# arm_femur_wLED_smd.net
KiCad netlist of a schematic drawn in EAGLE
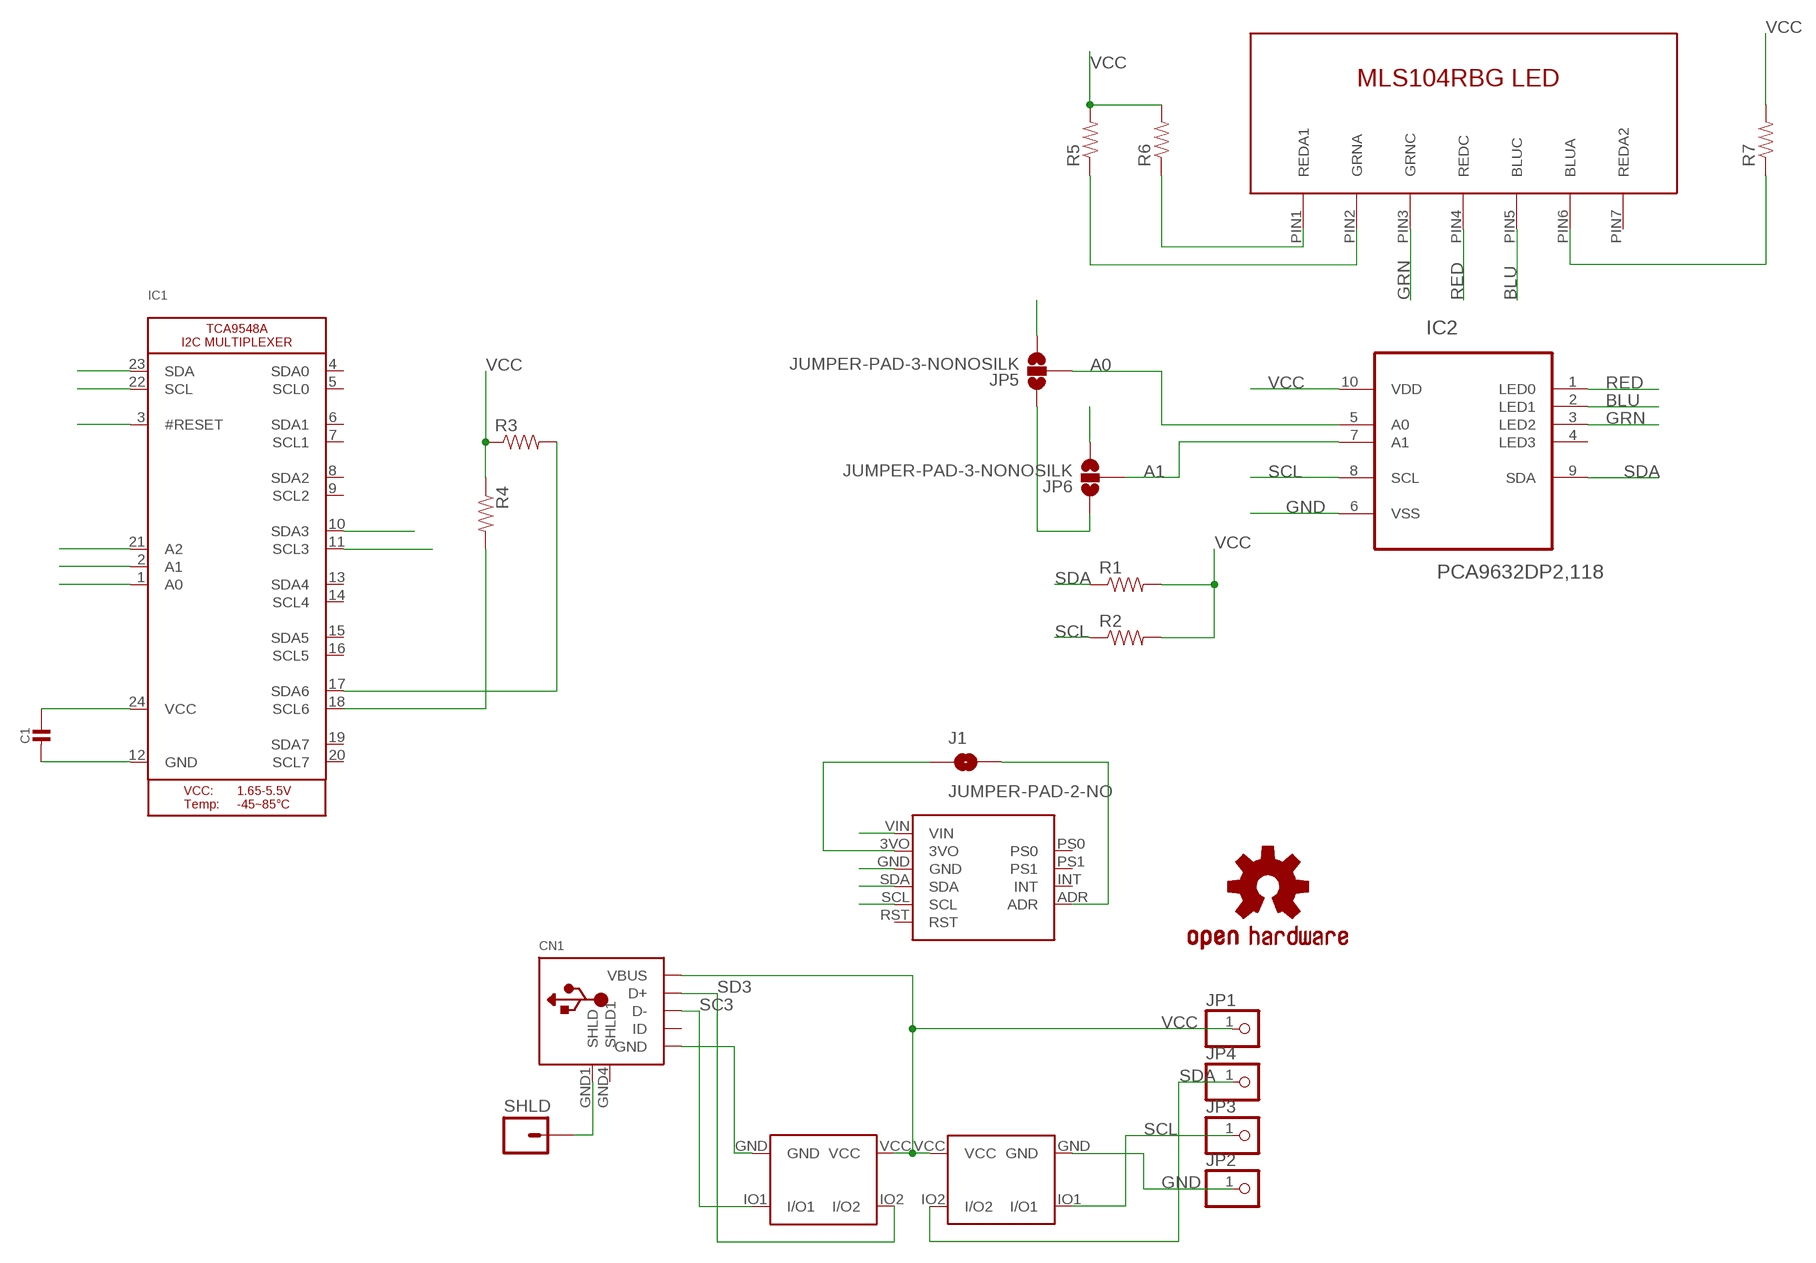
[diagram p0: schematic, sheet 1]

(export (version "E")
  (design (tool "Eeschema 10.0.6"))
  (components
    (comp (ref "C1")
      (value "CAP_CERAMIC0805-NOTHERMALS")
      (footprint "eagle-import:0805_NOTHERMALS")
      (libsource (lib "eagle-import") (part "CAP_CERAMIC0805-NOTHERMALS"))
    )
    (comp (ref "CN1")
      (value "USB")
      (footprint "eagle-import:USB-MINIB-THM-MOLEX_NOSLK")
      (libsource (lib "eagle-import") (part "USB"))
    )
    (comp (ref "IC1")
      (value "TCA9548A")
      (footprint "eagle-import:TSSOP24")
      (libsource (lib "eagle-import") (part "TCA9548A"))
    )
    (comp (ref "IC2")
      (value "PCA9632DP2,118")
      (footprint "eagle-import:SOP50P490X110-10N")
      (libsource (lib "eagle-import") (part "PCA9632DP2,118"))
    )
    (comp (ref "J1")
      (value "JUMPER-PAD-2-NO")
      (footprint "eagle-import:PAD-JUMPER-2-NO_NO_SILK")
      (libsource (lib "eagle-import") (part "JUMPER-PAD-2-NO"))
    )
    (comp (ref "JP1")
      (value "PINHD-1X1CB")
      (footprint "eagle-import:1X01-CLEANBIG")
      (libsource (lib "eagle-import") (part "PINHD-1X1CB"))
    )
    (comp (ref "JP2")
      (value "PINHD-1X1CB")
      (footprint "eagle-import:1X01-CLEANBIG")
      (libsource (lib "eagle-import") (part "PINHD-1X1CB"))
    )
    (comp (ref "JP3")
      (value "PINHD-1X1CB")
      (footprint "eagle-import:1X01-CLEANBIG")
      (libsource (lib "eagle-import") (part "PINHD-1X1CB"))
    )
    (comp (ref "JP4")
      (value "PINHD-1X1CB")
      (footprint "eagle-import:1X01-CLEANBIG")
      (libsource (lib "eagle-import") (part "PINHD-1X1CB"))
    )
    (comp (ref "JP5")
      (value "JUMPER-PAD-3-NONOSILK")
      (footprint "eagle-import:PAD-JUMPER-3-NO_NO_SILK")
      (libsource (lib "eagle-import") (part "JUMPER-PAD-3-NONOSILK"))
    )
    (comp (ref "JP6")
      (value "JUMPER-PAD-3-NONOSILK")
      (footprint "eagle-import:PAD-JUMPER-3-NO_NO_SILK")
      (libsource (lib "eagle-import") (part "JUMPER-PAD-3-NONOSILK"))
    )
    (comp (ref "LOGO1")
      (value "OSHW-LOGOS")
      (footprint "eagle-import:OSHW-LOGO-S")
      (libsource (lib "eagle-import") (part "OSHW-LOGOS"))
    )
    (comp (ref "R1")
      (value "RESISTOR0603-RES")
      (footprint "eagle-import:0603-RES")
      (libsource (lib "eagle-import") (part "RESISTOR0603-RES"))
    )
    (comp (ref "R2")
      (value "RESISTOR0603-RES")
      (footprint "eagle-import:0603-RES")
      (libsource (lib "eagle-import") (part "RESISTOR0603-RES"))
    )
    (comp (ref "R3")
      (value "RESISTOR0603-RES")
      (footprint "eagle-import:0603-RES")
      (libsource (lib "eagle-import") (part "RESISTOR0603-RES"))
    )
    (comp (ref "R4")
      (value "RESISTOR0603-RES")
      (footprint "eagle-import:0603-RES")
      (libsource (lib "eagle-import") (part "RESISTOR0603-RES"))
    )
    (comp (ref "R5")
      (value "RESISTOR0603-RES")
      (footprint "eagle-import:0603-RES")
      (libsource (lib "eagle-import") (part "RESISTOR0603-RES"))
    )
    (comp (ref "R6")
      (value "RESISTOR0603-RES")
      (footprint "eagle-import:0603-RES")
      (libsource (lib "eagle-import") (part "RESISTOR0603-RES"))
    )
    (comp (ref "R7")
      (value "RESISTOR0603-RES")
      (footprint "eagle-import:0603-RES")
      (libsource (lib "eagle-import") (part "RESISTOR0603-RES"))
    )
    (comp (ref "SHLD")
      (value "M01PTH")
      (footprint "eagle-import:1X01")
      (libsource (lib "eagle-import") (part "M01PTH"))
    )
    (comp (ref "U$1")
      (value "BNO_055_BKOUT")
      (footprint "eagle-import:BNO_BKOUT")
      (libsource (lib "eagle-import") (part "BNO_055_BKOUT"))
    )
    (comp (ref "U$2")
      (value "MSL0104RGB")
      (footprint "eagle-import:7-SMD")
      (libsource (lib "eagle-import") (part "MSL0104RGB"))
    )
    (comp (ref "U$3")
      (value "TVS_ARRAY_CD143A")
      (footprint "eagle-import:SOT-143")
      (libsource (lib "eagle-import") (part "TVS_ARRAY_CD143A"))
    )
    (comp (ref "U$4")
      (value "TVS_ARRAY_CD143A")
      (footprint "eagle-import:SOT-143")
      (libsource (lib "eagle-import") (part "TVS_ARRAY_CD143A"))
    )
  )
  (nets
    (net (code "1") (name "/A0") (class "Default")
      (node (ref "IC2") (pin "5") (pinfunction "A0_5") (pintype "input"))
      (node (ref "JP5") (pin "2") (pinfunction "2_2") (pintype "passive"))
    )
    (net (code "2") (name "/A1") (class "Default")
      (node (ref "IC2") (pin "7") (pinfunction "A1_7") (pintype "input"))
      (node (ref "JP6") (pin "2") (pinfunction "2_2") (pintype "passive"))
    )
    (net (code "3") (name "/BLU") (class "Default")
      (node (ref "IC2") (pin "2") (pinfunction "LED1_2") (pintype "output"))
      (node (ref "U$2") (pin "PIN5") (pinfunction "BLUC_PIN5") (pintype "bidirectional"))
    )
    (net (code "4") (name "/GND") (class "Default")
      (node (ref "C1") (pin "2") (pinfunction "2_2") (pintype "passive"))
      (node (ref "CN1") (pin "GND") (pinfunction "GND_GND") (pintype "power_in"))
      (node (ref "IC1") (pin "12") (pinfunction "GND_12") (pintype "bidirectional"))
      (node (ref "IC1") (pin "2") (pinfunction "A1_2") (pintype "bidirectional"))
      (node (ref "IC1") (pin "21") (pinfunction "A2_21") (pintype "bidirectional"))
      (node (ref "IC2") (pin "6") (pinfunction "VSS_6") (pintype "power_in"))
      (node (ref "JP2") (pin "1") (pinfunction "1_1") (pintype "passive"))
      (node (ref "JP5") (pin "1") (pinfunction "1_1") (pintype "passive"))
      (node (ref "JP6") (pin "1") (pinfunction "1_1") (pintype "passive"))
      (node (ref "U$1") (pin "GND") (pinfunction "GND_GND") (pintype "bidirectional"))
      (node (ref "U$3") (pin "GND") (pinfunction "GND_GND") (pintype "power_in"))
      (node (ref "U$4") (pin "GND") (pinfunction "GND_GND") (pintype "power_in"))
    )
    (net (code "5") (name "/GRN") (class "Default")
      (node (ref "IC2") (pin "3") (pinfunction "LED2_3") (pintype "output"))
      (node (ref "U$2") (pin "PIN3") (pinfunction "GRNC_PIN3") (pintype "bidirectional"))
    )
    (net (code "6") (name "/RED") (class "Default")
      (node (ref "IC2") (pin "1") (pinfunction "LED0_1") (pintype "output"))
      (node (ref "U$2") (pin "PIN4") (pinfunction "REDC_PIN4") (pintype "bidirectional"))
    )
    (net (code "7") (name "/SC3") (class "Default")
      (node (ref "CN1") (pin "D-") (pinfunction "D-_D-") (pintype "bidirectional"))
      (node (ref "IC1") (pin "11") (pinfunction "SCL3_11") (pintype "bidirectional"))
      (node (ref "U$4") (pin "IO1") (pinfunction "I/O1_IO1") (pintype "bidirectional"))
    )
    (net (code "8") (name "/SC6") (class "Default")
      (node (ref "IC1") (pin "18") (pinfunction "SCL6_18") (pintype "bidirectional"))
      (node (ref "R4") (pin "2") (pinfunction "2_2") (pintype "passive"))
      (node (ref "U$1") (pin "SCL") (pinfunction "SCL_SCL") (pintype "bidirectional"))
    )
    (net (code "9") (name "/SCL") (class "Default")
      (node (ref "IC1") (pin "22") (pinfunction "SCL_22") (pintype "bidirectional"))
      (node (ref "IC2") (pin "8") (pinfunction "SCL_8") (pintype "input"))
      (node (ref "JP3") (pin "1") (pinfunction "1_1") (pintype "passive"))
      (node (ref "R2") (pin "1") (pinfunction "1_1") (pintype "passive"))
      (node (ref "U$3") (pin "IO1") (pinfunction "I/O1_IO1") (pintype "bidirectional"))
    )
    (net (code "10") (name "/SD3") (class "Default")
      (node (ref "CN1") (pin "D+") (pinfunction "D+_D+") (pintype "bidirectional"))
      (node (ref "IC1") (pin "10") (pinfunction "SDA3_10") (pintype "bidirectional"))
      (node (ref "U$4") (pin "IO2") (pinfunction "I/O2_IO2") (pintype "bidirectional"))
    )
    (net (code "11") (name "/SD6") (class "Default")
      (node (ref "IC1") (pin "17") (pinfunction "SDA6_17") (pintype "bidirectional"))
      (node (ref "R3") (pin "2") (pinfunction "2_2") (pintype "passive"))
      (node (ref "U$1") (pin "SDA") (pinfunction "SDA_SDA") (pintype "bidirectional"))
    )
    (net (code "12") (name "/SDA") (class "Default")
      (node (ref "IC1") (pin "23") (pinfunction "SDA_23") (pintype "bidirectional"))
      (node (ref "IC2") (pin "9") (pinfunction "SDA_9") (pintype "bidirectional"))
      (node (ref "JP4") (pin "1") (pinfunction "1_1") (pintype "passive"))
      (node (ref "R1") (pin "1") (pinfunction "1_1") (pintype "passive"))
      (node (ref "U$3") (pin "IO2") (pinfunction "I/O2_IO2") (pintype "bidirectional"))
    )
    (net (code "13") (name "/VCC") (class "Default")
      (node (ref "C1") (pin "1") (pinfunction "1_1") (pintype "passive"))
      (node (ref "CN1") (pin "VBUS") (pinfunction "VBUS_VBUS") (pintype "power_in"))
      (node (ref "IC1") (pin "1") (pinfunction "A0_1") (pintype "bidirectional"))
      (node (ref "IC1") (pin "24") (pinfunction "VCC_24") (pintype "bidirectional"))
      (node (ref "IC1") (pin "3") (pinfunction "#RESET_3") (pintype "bidirectional"))
      (node (ref "IC2") (pin "10") (pinfunction "VDD_10") (pintype "power_in"))
      (node (ref "JP1") (pin "1") (pinfunction "1_1") (pintype "passive"))
      (node (ref "JP5") (pin "3") (pinfunction "3_3") (pintype "passive"))
      (node (ref "JP6") (pin "3") (pinfunction "3_3") (pintype "passive"))
      (node (ref "R1") (pin "2") (pinfunction "2_2") (pintype "passive"))
      (node (ref "R2") (pin "2") (pinfunction "2_2") (pintype "passive"))
      (node (ref "R3") (pin "1") (pinfunction "1_1") (pintype "passive"))
      (node (ref "R4") (pin "1") (pinfunction "1_1") (pintype "passive"))
      (node (ref "R5") (pin "2") (pinfunction "2_2") (pintype "passive"))
      (node (ref "R6") (pin "2") (pinfunction "2_2") (pintype "passive"))
      (node (ref "R7") (pin "2") (pinfunction "2_2") (pintype "passive"))
      (node (ref "U$1") (pin "VIN") (pinfunction "VIN_VIN") (pintype "bidirectional"))
      (node (ref "U$3") (pin "VCC") (pinfunction "VCC_VCC") (pintype "power_in"))
      (node (ref "U$4") (pin "VCC") (pinfunction "VCC_VCC") (pintype "power_in"))
    )
    (net (code "14") (name "Net-(CN1-SHLD)") (class "Default")
      (node (ref "CN1") (pin "GND1") (pinfunction "SHLD_GND1") (pintype "bidirectional"))
      (node (ref "SHLD") (pin "1") (pinfunction "1_1") (pintype "passive"))
    )
    (net (code "15") (name "Net-(J1-Pad1)") (class "Default")
      (node (ref "J1") (pin "1") (pinfunction "1_1") (pintype "passive"))
      (node (ref "U$1") (pin "3VO") (pinfunction "3VO_3VO") (pintype "bidirectional"))
    )
    (net (code "16") (name "Net-(J1-Pad2)") (class "Default")
      (node (ref "J1") (pin "2") (pinfunction "2_2") (pintype "passive"))
      (node (ref "U$1") (pin "ADR") (pinfunction "ADR_ADR") (pintype "bidirectional"))
    )
    (net (code "17") (name "Net-(U$2-BLUA)") (class "Default")
      (node (ref "R7") (pin "1") (pinfunction "1_1") (pintype "passive"))
      (node (ref "U$2") (pin "PIN6") (pinfunction "BLUA_PIN6") (pintype "bidirectional"))
    )
    (net (code "18") (name "Net-(U$2-GRNA)") (class "Default")
      (node (ref "R5") (pin "1") (pinfunction "1_1") (pintype "passive"))
      (node (ref "U$2") (pin "PIN2") (pinfunction "GRNA_PIN2") (pintype "bidirectional"))
    )
    (net (code "19") (name "Net-(U$2-REDA1)") (class "Default")
      (node (ref "R6") (pin "1") (pinfunction "1_1") (pintype "passive"))
      (node (ref "U$2") (pin "PIN1") (pinfunction "REDA1_PIN1") (pintype "bidirectional"))
    )
    (net (code "20") (name "unconnected-(CN1-PadID)") (class "Default")
      (node (ref "CN1") (pin "ID") (pinfunction "ID_ID") (pintype "bidirectional"))
    )
    (net (code "21") (name "unconnected-(CN1-SHLD1-PadGND4)") (class "Default")
      (node (ref "CN1") (pin "GND4") (pinfunction "SHLD1_GND4") (pintype "bidirectional"))
    )
    (net (code "22") (name "unconnected-(IC1-SCL0-Pad5)") (class "Default")
      (node (ref "IC1") (pin "5") (pinfunction "SCL0_5") (pintype "bidirectional"))
    )
    (net (code "23") (name "unconnected-(IC1-SCL1-Pad7)") (class "Default")
      (node (ref "IC1") (pin "7") (pinfunction "SCL1_7") (pintype "bidirectional"))
    )
    (net (code "24") (name "unconnected-(IC1-SCL2-Pad9)") (class "Default")
      (node (ref "IC1") (pin "9") (pinfunction "SCL2_9") (pintype "bidirectional"))
    )
    (net (code "25") (name "unconnected-(IC1-SCL4-Pad14)") (class "Default")
      (node (ref "IC1") (pin "14") (pinfunction "SCL4_14") (pintype "bidirectional"))
    )
    (net (code "26") (name "unconnected-(IC1-SCL5-Pad16)") (class "Default")
      (node (ref "IC1") (pin "16") (pinfunction "SCL5_16") (pintype "bidirectional"))
    )
    (net (code "27") (name "unconnected-(IC1-SCL7-Pad20)") (class "Default")
      (node (ref "IC1") (pin "20") (pinfunction "SCL7_20") (pintype "bidirectional"))
    )
    (net (code "28") (name "unconnected-(IC1-SDA0-Pad4)") (class "Default")
      (node (ref "IC1") (pin "4") (pinfunction "SDA0_4") (pintype "bidirectional"))
    )
    (net (code "29") (name "unconnected-(IC1-SDA1-Pad6)") (class "Default")
      (node (ref "IC1") (pin "6") (pinfunction "SDA1_6") (pintype "bidirectional"))
    )
    (net (code "30") (name "unconnected-(IC1-SDA2-Pad8)") (class "Default")
      (node (ref "IC1") (pin "8") (pinfunction "SDA2_8") (pintype "bidirectional"))
    )
    (net (code "31") (name "unconnected-(IC1-SDA4-Pad13)") (class "Default")
      (node (ref "IC1") (pin "13") (pinfunction "SDA4_13") (pintype "bidirectional"))
    )
    (net (code "32") (name "unconnected-(IC1-SDA5-Pad15)") (class "Default")
      (node (ref "IC1") (pin "15") (pinfunction "SDA5_15") (pintype "bidirectional"))
    )
    (net (code "33") (name "unconnected-(IC1-SDA7-Pad19)") (class "Default")
      (node (ref "IC1") (pin "19") (pinfunction "SDA7_19") (pintype "bidirectional"))
    )
    (net (code "34") (name "unconnected-(IC2-LED3-Pad4)") (class "Default")
      (node (ref "IC2") (pin "4") (pinfunction "LED3_4") (pintype "output"))
    )
    (net (code "35") (name "unconnected-(U$1-PadINT)") (class "Default")
      (node (ref "U$1") (pin "INT") (pinfunction "INT_INT") (pintype "bidirectional"))
    )
    (net (code "36") (name "unconnected-(U$1-PadPS0)") (class "Default")
      (node (ref "U$1") (pin "PS0") (pinfunction "PS0_PS0") (pintype "bidirectional"))
    )
    (net (code "37") (name "unconnected-(U$1-PadPS1)") (class "Default")
      (node (ref "U$1") (pin "PS1") (pinfunction "PS1_PS1") (pintype "bidirectional"))
    )
    (net (code "38") (name "unconnected-(U$1-PadRST)") (class "Default")
      (node (ref "U$1") (pin "RST") (pinfunction "RST_RST") (pintype "bidirectional"))
    )
    (net (code "39") (name "unconnected-(U$2-REDA2-PadPIN7)") (class "Default")
      (node (ref "U$2") (pin "PIN7") (pinfunction "REDA2_PIN7") (pintype "bidirectional"))
    )
  )
)
